# power.net
KiCad netlist of a schematic drawn in Altium Designer
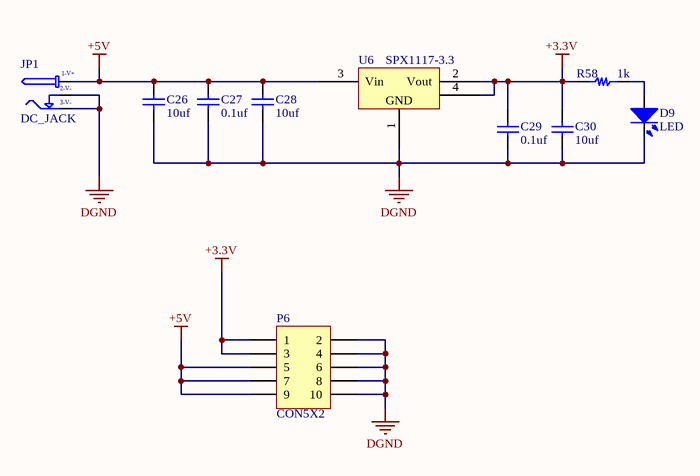
[diagram p0: power.SchDoc]

(export (version "E")
  (design (tool "Eeschema 10.0.6"))
  (components
    (comp (ref "C26")
      (value "10uf")
      (footprint "0805C")
      (description "贴片电容")
      (fields (field (name "PUBLISHER") "Altium Limited"))
      (libsource (lib "Device_CHT") (part "Cap"))
    )
    (comp (ref "C27")
      (value "0.1uf")
      (footprint "0805C")
      (description "贴片电容")
      (fields (field (name "PUBLISHER") "Altium Limited"))
      (libsource (lib "Device_CHT") (part "Cap"))
    )
    (comp (ref "C28")
      (value "10uf")
      (footprint "0805C")
      (description "贴片电容")
      (fields (field (name "PUBLISHER") "Altium Limited"))
      (libsource (lib "Device_CHT") (part "Cap"))
    )
    (comp (ref "C29")
      (value "0.1uf")
      (footprint "0805C")
      (description "贴片电容")
      (fields (field (name "PUBLISHER") "Altium Limited"))
      (libsource (lib "Device_CHT") (part "Cap"))
    )
    (comp (ref "C30")
      (value "10uf")
      (footprint "0805C")
      (description "贴片电容")
      (fields (field (name "PUBLISHER") "Altium Limited"))
      (libsource (lib "Device_CHT") (part "Cap"))
    )
    (comp (ref "D9")
      (value "LED")
      (footprint "0805-LED-RED")
      (description "Typical INFRARED GaAs LED")
      (fields (field (name "PUBLISHER") "Altium Limited"))
      (libsource (lib "Device_CHT") (part "LED"))
    )
    (comp (ref "JP1")
      (value "DC_JACK")
      (footprint "DC3")
      (description "DC电源接口")
      (libsource (lib "Device_CHT") (part "DC_JACK"))
    )
    (comp (ref "P6")
      (value "CON5X2")
      (footprint "HDR2X5-2.54MM")
      (description "Header, 5-Pin, Dual row")
      (fields (field (name "PUBLISHER") "Altium Limited"))
      (libsource (lib "Connector_Veiko") (part "CON5X2"))
    )
    (comp (ref "R58")
      (value "1k")
      (footprint "0805_small")
      (description "电阻")
      (fields (field (name "PUBLISHER") "Altium Limited"))
      (libsource (lib "Device_CHT") (part "Res"))
    )
    (comp (ref "U6")
      (value "SPX1117-3.3")
      (footprint "SOT-223(DCY4)")
      (libsource (lib "Device_CHT") (part "SPX1117"))
    )
  )
  (nets
    (net (code "1") (name "+3.3V") (class "Default")
      (node (ref "C29") (pin "2") (pinfunction "2_2") (pintype "passive"))
      (node (ref "C30") (pin "2") (pinfunction "2_2") (pintype "passive"))
      (node (ref "P6") (pin "1") (pinfunction "1_1") (pintype "passive"))
      (node (ref "P6") (pin "3") (pinfunction "3_3") (pintype "passive"))
      (node (ref "R58") (pin "2") (pinfunction "2_2") (pintype "passive"))
      (node (ref "U6") (pin "2") (pinfunction "Vout_2") (pintype "passive"))
      (node (ref "U6") (pin "4") (pintype "passive"))
    )
    (net (code "2") (name "+5V") (class "Default")
      (node (ref "C26") (pin "2") (pinfunction "2_2") (pintype "passive"))
      (node (ref "C27") (pin "2") (pinfunction "2_2") (pintype "passive"))
      (node (ref "C28") (pin "2") (pinfunction "2_2") (pintype "passive"))
      (node (ref "JP1") (pin "1") (pinfunction "1_1") (pintype "passive"))
      (node (ref "P6") (pin "5") (pinfunction "5_5") (pintype "passive"))
      (node (ref "P6") (pin "7") (pinfunction "7_7") (pintype "passive"))
      (node (ref "P6") (pin "9") (pinfunction "9_9") (pintype "passive"))
      (node (ref "U6") (pin "3") (pinfunction "Vin_3") (pintype "passive"))
    )
    (net (code "3") (name "DGND") (class "Default")
      (node (ref "C26") (pin "1") (pinfunction "1_1") (pintype "passive"))
      (node (ref "C27") (pin "1") (pinfunction "1_1") (pintype "passive"))
      (node (ref "C28") (pin "1") (pinfunction "1_1") (pintype "passive"))
      (node (ref "C29") (pin "1") (pinfunction "1_1") (pintype "passive"))
      (node (ref "C30") (pin "1") (pinfunction "1_1") (pintype "passive"))
      (node (ref "D9") (pin "2") (pinfunction "K_2") (pintype "passive"))
      (node (ref "JP1") (pin "2") (pinfunction "2_2") (pintype "passive"))
      (node (ref "JP1") (pin "3") (pinfunction "3_3") (pintype "passive"))
      (node (ref "P6") (pin "10") (pinfunction "10_10") (pintype "passive"))
      (node (ref "P6") (pin "2") (pinfunction "2_2") (pintype "passive"))
      (node (ref "P6") (pin "4") (pinfunction "4_4") (pintype "passive"))
      (node (ref "P6") (pin "6") (pinfunction "6_6") (pintype "passive"))
      (node (ref "P6") (pin "8") (pinfunction "8_8") (pintype "passive"))
      (node (ref "U6") (pin "1") (pintype "passive"))
    )
    (net (code "4") (name "Net-(D9-A)") (class "Default")
      (node (ref "D9") (pin "1") (pinfunction "A_1") (pintype "passive"))
      (node (ref "R58") (pin "1") (pinfunction "1_1") (pintype "passive"))
    )
  )
)
